# 02_DAC_Audio.net
KiCad netlist of a schematic drawn in Altium Designer
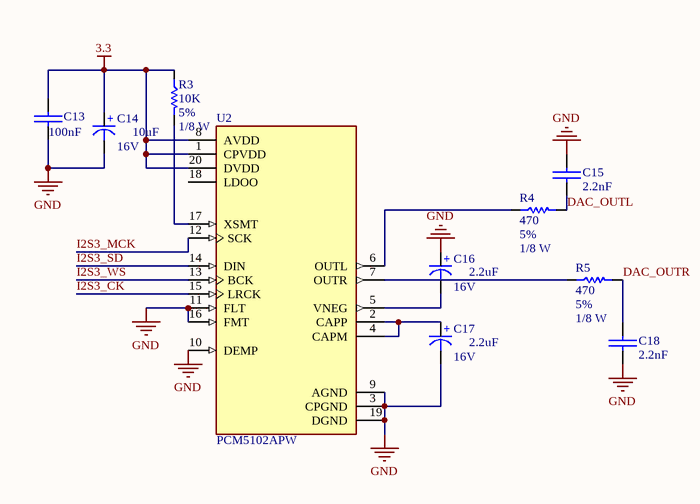
[diagram p0: 02_DAC_Audio.SchDoc]

(export (version "E")
  (design (tool "Eeschema 10.0.6"))
  (components
    (comp (ref "C13")
      (value "100nF")
      (footprint "SMD_CAP_1206")
      (description "Bipolar Capacitor")
      (fields (field (name "VOLTAGE") "100V") (field (name "DESIGNER") "Saeid Jorablo"))
      (libsource (lib "My Library") (part "Cap-Bipolar"))
    )
    (comp (ref "C14")
      (value "10uF")
      (footprint "cap 01")
      (description "Polar Capacitor")
      (fields (field (name "VOLTAGE") "16V") (field (name "DESIGNER") "Saeid Jorablo"))
      (libsource (lib "My Library") (part "Cap-Polar"))
    )
    (comp (ref "C15")
      (value "2.2nF")
      (footprint "SMD_CAP_1206")
      (description "Bipolar Capacitor")
      (fields (field (name "VOLTAGE") "100V") (field (name "DESIGNER") "Saeid Jorablo"))
      (libsource (lib "My Library") (part "Cap-Bipolar"))
    )
    (comp (ref "C16")
      (value "2.2uF")
      (footprint "cap 01")
      (description "Polar Capacitor")
      (fields (field (name "VOLTAGE") "16V") (field (name "DESIGNER") "Saeid Jorablo"))
      (libsource (lib "My Library") (part "Cap-Polar"))
    )
    (comp (ref "C17")
      (value "2.2uF")
      (footprint "cap 01")
      (description "Polar Capacitor")
      (fields (field (name "VOLTAGE") "16V") (field (name "DESIGNER") "Saeid Jorablo"))
      (libsource (lib "My Library") (part "Cap-Polar"))
    )
    (comp (ref "C18")
      (value "2.2nF")
      (footprint "SMD_CAP_1206")
      (description "Bipolar Capacitor")
      (fields (field (name "VOLTAGE") "100V") (field (name "DESIGNER") "Saeid Jorablo"))
      (libsource (lib "My Library") (part "Cap-Bipolar"))
    )
    (comp (ref "R3")
      (value "10K")
      (footprint "RES 0805 (2012X06L)")
      (description "Resistor")
      (fields (field (name "TOLERANCE") "5%") (field (name "POWER") "1/8 W"))
      (libsource (lib "My Library") (part "Resistor"))
    )
    (comp (ref "R4")
      (value "470")
      (footprint "RES 0805 (2012X06L)")
      (description "Resistor")
      (fields (field (name "TOLERANCE") "5%") (field (name "POWER") "1/8 W"))
      (libsource (lib "My Library") (part "Resistor"))
    )
    (comp (ref "R5")
      (value "470")
      (footprint "RES 0805 (2012X06L)")
      (description "Resistor")
      (fields (field (name "TOLERANCE") "5%") (field (name "POWER") "1/8 W"))
      (libsource (lib "My Library") (part "Resistor"))
    )
    (comp (ref "U2")
      (value "PCM5102APW")
      (footprint "SOP65P640X120-20N")
      (fields (field (name "MF") "Texas Instruments"))
      (libsource (lib "PCM5102APW") (part "PCM5102APW"))
    )
  )
  (nets
    (net (code "1") (name "/DAC_OUTL") (class "Default")
      (node (ref "C15") (pin "2") (pinfunction "-_2") (pintype "passive"))
      (node (ref "R4") (pin "2") (pinfunction "2_2") (pintype "passive"))
    )
    (net (code "2") (name "/DAC_OUTR") (class "Default")
      (node (ref "C18") (pin "1") (pinfunction "+_1") (pintype "passive"))
      (node (ref "R5") (pin "2") (pinfunction "2_2") (pintype "passive"))
    )
    (net (code "3") (name "/I2S3_CK") (class "Default")
      (node (ref "U2") (pin "15") (pinfunction "LRCK_15") (pintype "input"))
    )
    (net (code "4") (name "/I2S3_MCK") (class "Default")
      (node (ref "U2") (pin "12") (pinfunction "SCK_12") (pintype "input"))
    )
    (net (code "5") (name "/I2S3_SD") (class "Default")
      (node (ref "U2") (pin "14") (pinfunction "DIN_14") (pintype "input"))
    )
    (net (code "6") (name "/I2S3_WS") (class "Default")
      (node (ref "U2") (pin "13") (pinfunction "BCK_13") (pintype "input"))
    )
    (net (code "7") (name "3.3") (class "Default")
      (node (ref "C13") (pin "1") (pinfunction "+_1") (pintype "passive"))
      (node (ref "C14") (pin "1") (pinfunction "+_1") (pintype "passive"))
      (node (ref "R3") (pin "1") (pinfunction "1_1") (pintype "passive"))
      (node (ref "U2") (pin "1") (pinfunction "CPVDD_1") (pintype "power_in"))
      (node (ref "U2") (pin "20") (pinfunction "DVDD_20") (pintype "power_in"))
      (node (ref "U2") (pin "8") (pinfunction "AVDD_8") (pintype "power_in"))
    )
    (net (code "8") (name "GND") (class "Default")
      (node (ref "C13") (pin "2") (pinfunction "-_2") (pintype "passive"))
      (node (ref "C14") (pin "2") (pinfunction "-_2") (pintype "passive"))
      (node (ref "C15") (pin "1") (pinfunction "+_1") (pintype "passive"))
      (node (ref "C16") (pin "1") (pinfunction "+_1") (pintype "passive"))
      (node (ref "C17") (pin "2") (pinfunction "-_2") (pintype "passive"))
      (node (ref "C18") (pin "2") (pinfunction "-_2") (pintype "passive"))
      (node (ref "U2") (pin "10") (pinfunction "DEMP_10") (pintype "input"))
      (node (ref "U2") (pin "11") (pinfunction "FLT_11") (pintype "input"))
      (node (ref "U2") (pin "16") (pinfunction "FMT_16") (pintype "input"))
      (node (ref "U2") (pin "19") (pinfunction "DGND_19") (pintype "power_in"))
      (node (ref "U2") (pin "3") (pinfunction "CPGND_3") (pintype "power_in"))
      (node (ref "U2") (pin "9") (pinfunction "AGND_9") (pintype "power_in"))
    )
    (net (code "9") (name "Net-(C16--)") (class "Default")
      (node (ref "C16") (pin "2") (pinfunction "-_2") (pintype "passive"))
      (node (ref "U2") (pin "5") (pinfunction "VNEG_5") (pintype "output"))
    )
    (net (code "10") (name "Net-(C17-+)") (class "Default")
      (node (ref "C17") (pin "1") (pinfunction "+_1") (pintype "passive"))
      (node (ref "U2") (pin "2") (pinfunction "CAPP_2") (pintype "passive"))
      (node (ref "U2") (pin "4") (pinfunction "CAPM_4") (pintype "passive"))
    )
    (net (code "11") (name "Net-(U2-OUTL)") (class "Default")
      (node (ref "R4") (pin "1") (pinfunction "1_1") (pintype "passive"))
      (node (ref "U2") (pin "6") (pinfunction "OUTL_6") (pintype "output"))
    )
    (net (code "12") (name "Net-(U2-OUTR)") (class "Default")
      (node (ref "R5") (pin "1") (pinfunction "1_1") (pintype "passive"))
      (node (ref "U2") (pin "7") (pinfunction "OUTR_7") (pintype "output"))
    )
    (net (code "13") (name "Net-(U2-XSMT)") (class "Default")
      (node (ref "R3") (pin "2") (pinfunction "2_2") (pintype "passive"))
      (node (ref "U2") (pin "17") (pinfunction "XSMT_17") (pintype "input"))
    )
    (net (code "14") (name "unconnected-(U2-LDOO-Pad18)") (class "Default")
      (node (ref "U2") (pin "18") (pinfunction "LDOO_18") (pintype "power_in"))
    )
  )
)
